# MRX80SQUARE.net
KiCad netlist of a schematic drawn in Altium Designer
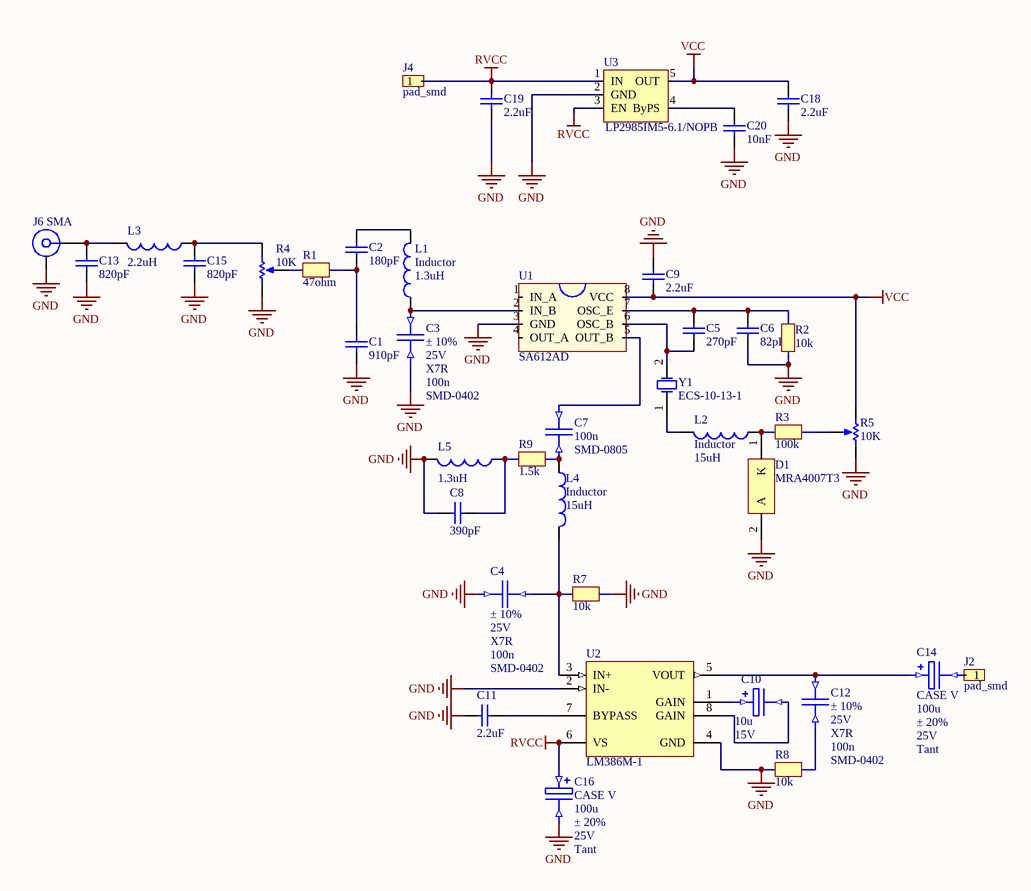
[diagram p0: MRX80SQUARE.SchDoc]

(export (version "E")
  (design (tool "Eeschema 10.0.6"))
  (components
    (comp (ref "C1")
      (value "910pF")
      (footprint "0402")
      (description "Capacitor (Semiconductor SIM Model)")
      (fields (field (name "Comment") "Cap Semi") (field (name "PUBLISHER") "Altium Limited"))
      (libsource (lib "Miscellaneous Devices") (part "Cap Semi"))
    )
    (comp (ref "C2")
      (value "180pF")
      (footprint "0402")
      (description "Capacitor (Semiconductor SIM Model)")
      (fields (field (name "Comment") "Cap Semi") (field (name "PUBLISHER") "Altium Limited"))
      (libsource (lib "Miscellaneous Devices") (part "Cap Semi"))
    )
    (comp (ref "C3")
      (value "100n")
      (footprint "CAPC1005X04N_0402")
      (description "Class 1 SMD Capacitor")
      (fields
        (field (name "MANUFACTURER") "MULTICOMP")
        (field (name "TOLERANCE") "± 10%")
        (field (name "VOLTAGE") "25V")
        (field (name "TYPE") "X7R")
        (field (name "PACKAGEREFERENCE") "SMD-0402")
        (field (name "Comment") "Capacitor")
        (field (name "PUBLISHER") "atr")
      )
      (libsource (lib "AQA_20007_4_Flange") (part "Capacitor_100n_0402_Bulk"))
    )
    (comp (ref "C4")
      (value "100n")
      (footprint "CAPC1005X04N_0402")
      (description "Class 1 SMD Capacitor")
      (fields
        (field (name "MANUFACTURER") "MULTICOMP")
        (field (name "TOLERANCE") "± 10%")
        (field (name "VOLTAGE") "25V")
        (field (name "TYPE") "X7R")
        (field (name "PACKAGEREFERENCE") "SMD-0402")
        (field (name "Comment") "Capacitor")
        (field (name "PUBLISHER") "atr")
      )
      (libsource (lib "AQA_20007_4_Flange") (part "Capacitor_100n_0402_Bulk"))
    )
    (comp (ref "C5")
      (value "270pF")
      (footprint "0402")
      (description "Capacitor (Semiconductor SIM Model)")
      (fields (field (name "Comment") "Cap Semi") (field (name "PUBLISHER") "Altium Limited"))
      (libsource (lib "Miscellaneous Devices") (part "Cap Semi"))
    )
    (comp (ref "C6")
      (value "82pF")
      (footprint "0402")
      (description "Capacitor (Semiconductor SIM Model)")
      (fields (field (name "Comment") "Cap Semi") (field (name "PUBLISHER") "Altium Limited"))
      (libsource (lib "Miscellaneous Devices") (part "Cap Semi"))
    )
    (comp (ref "C7")
      (value "100n")
      (footprint "CAPC2012X06N_0806")
      (description "Class 1 SMD Capacitor")
      (fields
        (field (name "MANUFACTURER") "Kemet")
        (field (name "TOLERANCE") "± 5%")
        (field (name "PACKAGEREFERENCE") "SMD-0805")
        (field (name "PUBLISHER") "atr")
      )
      (libsource (lib "AQA_atr_2013") (part "Capacitor_47n_0805_C0G"))
    )
    (comp (ref "C8")
      (value "390pF")
      (footprint "0402")
      (description "Capacitor (Semiconductor SIM Model)")
      (fields (field (name "Comment") "Cap Semi") (field (name "PUBLISHER") "Altium Limited"))
      (libsource (lib "Miscellaneous Devices") (part "Cap Semi"))
    )
    (comp (ref "C9")
      (value "2.2uF")
      (footprint "0402")
      (description "Capacitor (Semiconductor SIM Model)")
      (fields (field (name "Comment") "Cap Semi") (field (name "PUBLISHER") "Altium Limited"))
      (libsource (lib "Miscellaneous Devices") (part "Cap Semi"))
    )
    (comp (ref "C10")
      (value "10u")
      (footprint "CAP_CASE_B_1210_m3225")
      (description "Tant SMD Capacitor")
      (fields
        (field (name "MANUFACTURER") "AVX")
        (field (name "TOLERANCE") "± 20%")
        (field (name "VOLTAGE") "15V")
        (field (name "PUBLISHER") "atr")
      )
      (libsource (lib "AQA_atr_2013") (part "Capacitor_100u_Tant_SMD_CASE_B_m3525"))
    )
    (comp (ref "C11")
      (value "2.2uF")
      (footprint "0402")
      (description "Capacitor (Semiconductor SIM Model)")
      (fields (field (name "Comment") "Cap Semi") (field (name "PUBLISHER") "Altium Limited"))
      (libsource (lib "Miscellaneous Devices") (part "Cap Semi"))
    )
    (comp (ref "C12")
      (value "100n")
      (footprint "CAPC1005X04N_0402")
      (description "Class 1 SMD Capacitor")
      (fields
        (field (name "MANUFACTURER") "MULTICOMP")
        (field (name "TOLERANCE") "± 10%")
        (field (name "VOLTAGE") "25V")
        (field (name "TYPE") "X7R")
        (field (name "PACKAGEREFERENCE") "SMD-0402")
        (field (name "Comment") "Capacitor")
        (field (name "PUBLISHER") "atr")
      )
      (libsource (lib "AQA_20007_4_Flange") (part "Capacitor_100n_0402_Bulk"))
    )
    (comp (ref "C13")
      (value "820pF")
      (footprint "0402")
      (description "Capacitor (Semiconductor SIM Model)")
      (fields (field (name "Comment") "Cap Semi") (field (name "PUBLISHER") "Altium Limited"))
      (libsource (lib "Miscellaneous Devices") (part "Cap Semi"))
    )
    (comp (ref "C14")
      (value "100u")
      (footprint "CAP_CASE_V_2924_m7361-38")
      (description "Tant SMD Capacitor")
      (fields
        (field (name "MANUFACTURER") "AVX")
        (field (name "PACKAGEDESCRIPTION") "CASE V")
        (field (name "TOLERANCE") "± 20%")
        (field (name "VOLTAGE") "25V")
        (field (name "TYPE") "Tant")
        (field (name "Comment") "Capacitor")
        (field (name "PUBLISHER") "atr")
      )
      (libsource (lib "") (part "Capacitor_100u_Tant_SMD_CASE_V_m7361_1"))
    )
    (comp (ref "C15")
      (value "820pF")
      (footprint "0402")
      (description "Capacitor (Semiconductor SIM Model)")
      (fields (field (name "Comment") "Cap Semi") (field (name "PUBLISHER") "Altium Limited"))
      (libsource (lib "Miscellaneous Devices") (part "Cap Semi"))
    )
    (comp (ref "C16")
      (value "100u")
      (footprint "CAP_CASE_V_2924_m7361-38")
      (description "Tant SMD Capacitor")
      (fields
        (field (name "MANUFACTURER") "AVX")
        (field (name "PACKAGEDESCRIPTION") "CASE V")
        (field (name "TOLERANCE") "± 20%")
        (field (name "VOLTAGE") "25V")
        (field (name "TYPE") "Tant")
        (field (name "Comment") "Capacitor")
        (field (name "PUBLISHER") "atr")
      )
      (libsource (lib "AQA_20007_4_Flange") (part "Capacitor_100u_Tant_SMD_CASE_V_m7361"))
    )
    (comp (ref "C18")
      (value "2.2uF")
      (footprint "0402")
      (description "Capacitor (Semiconductor SIM Model)")
      (fields (field (name "Comment") "Cap Semi") (field (name "PUBLISHER") "Altium Limited"))
      (libsource (lib "Miscellaneous Devices") (part "Cap Semi"))
    )
    (comp (ref "C19")
      (value "2.2uF")
      (footprint "0402")
      (description "Capacitor (Semiconductor SIM Model)")
      (fields (field (name "Comment") "Cap Semi") (field (name "PUBLISHER") "Altium Limited"))
      (libsource (lib "Miscellaneous Devices") (part "Cap Semi"))
    )
    (comp (ref "C20")
      (value "10nF")
      (footprint "0402")
      (description "Capacitor (Semiconductor SIM Model)")
      (fields (field (name "Comment") "Cap Semi") (field (name "PUBLISHER") "Altium Limited"))
      (libsource (lib "Miscellaneous Devices") (part "Cap Semi"))
    )
    (comp (ref "D1")
      (value "MRA4007T3")
      (footprint "ONSC-SMA-2-403D-02_V")
      (description "Surface Mount Standard Recovery Power Rectifier, 2-Pin SMA, Tape and Reel")
      (fields (field (name "MANUFACTURER") "On Semiconductor"))
      (libsource (lib "ON Semi Rectifiers") (part "MRA4007T3"))
    )
    (comp (ref "J2")
      (value "pad_smd")
      (footprint "pad_smd_bodge")
      (description "1mm * 2mm smd pad")
      (libsource (lib "") (part "pad_smd_1mm*2mm_1"))
    )
    (comp (ref "J4")
      (value "pad_smd")
      (footprint "pad_smd_bodge")
      (description "1mm * 2mm smd pad")
      (libsource (lib "AQA_Ismolib") (part "pad_smd_1mm*2mm"))
    )
    (comp (ref "J6")
      (value "SMA")
      (footprint "ROS-32K145-400L5_V")
      (description "SMA Right Angle Jack, Edge Mount, Up to 18 GHz, -55 to 155 degC")
      (fields (field (name "PARTNUMBER") "32K145-400L5"))
      (libsource (lib "Rosenberger SMA") (part "32K145-400L5"))
    )
    (comp (ref "L1")
      (value "Inductor")
      (footprint "0402-A")
      (fields (field (name "ALTIUM_VALUE") "1.3uH") (field (name "PUBLISHER") "Altium Limited"))
      (libsource (lib "Miscellaneous Devices") (part "Inductor"))
    )
    (comp (ref "L2")
      (value "Inductor")
      (footprint "0402-A")
      (fields (field (name "ALTIUM_VALUE") "15uH") (field (name "PUBLISHER") "Altium Limited"))
      (libsource (lib "Miscellaneous Devices") (part "Inductor"))
    )
    (comp (ref "L3")
      (value "2.2uH")
      (footprint "0603")
      (description "Inductor")
      (fields (field (name "PUBLISHER") "Altium Limited"))
      (libsource (lib "Miscellaneous Devices") (part "Inductor"))
    )
    (comp (ref "L4")
      (value "Inductor")
      (footprint "0402-A")
      (fields (field (name "ALTIUM_VALUE") "15uH") (field (name "PUBLISHER") "Altium Limited"))
      (libsource (lib "Miscellaneous Devices") (part "Inductor"))
    )
    (comp (ref "L5")
      (value "1.3uH")
      (footprint "0402-A")
      (description "Inductor")
      (fields (field (name "PUBLISHER") "Altium Limited"))
      (libsource (lib "Miscellaneous Devices") (part "Inductor"))
    )
    (comp (ref "R1")
      (value "47ohm")
      (footprint "RESC1005X04N_0402")
      (description "Generic SMD Resistor")
      (fields
        (field (name "MANUFACTURER") "SUSUMU")
        (field (name "VOLTAGE") "75V")
        (field (name "PUBLISHER") "atr")
      )
      (libsource (lib "AQA_atr_2013") (part "Resistor_SMD_Generic"))
    )
    (comp (ref "R2")
      (value "10k")
      (footprint "RESC1005X04N_0402")
      (description "Generic SMD Resistor")
      (fields
        (field (name "MANUFACTURER") "SUSUMU")
        (field (name "VOLTAGE") "75V")
        (field (name "PUBLISHER") "atr")
      )
      (libsource (lib "") (part "Resistor_SMD_Generic_2"))
    )
    (comp (ref "R3")
      (value "100k")
      (footprint "RESC1005X04N_0402")
      (description "Generic SMD Resistor")
      (fields
        (field (name "MANUFACTURER") "SUSUMU")
        (field (name "VOLTAGE") "75V")
        (field (name "PUBLISHER") "atr")
      )
      (libsource (lib "AQA_atr_2013") (part "Resistor_SMD_Generic"))
    )
    (comp (ref "R4")
      (value "10K")
      (footprint "VR5")
      (description "Potentiometer")
      (fields (field (name "Comment") "RPot") (field (name "PUBLISHER") "Altium Limited"))
      (libsource (lib "Miscellaneous Devices") (part "RPot"))
    )
    (comp (ref "R5")
      (value "10K")
      (footprint "VR5")
      (description "Potentiometer")
      (fields (field (name "Comment") "RPot") (field (name "PUBLISHER") "Altium Limited"))
      (libsource (lib "Miscellaneous Devices") (part "RPot"))
    )
    (comp (ref "R7")
      (value "10k")
      (footprint "RESC1005X04N_0402")
      (description "Generic SMD Resistor")
      (fields
        (field (name "MANUFACTURER") "SUSUMU")
        (field (name "VOLTAGE") "75V")
        (field (name "PUBLISHER") "atr")
      )
      (libsource (lib "") (part "Resistor_SMD_Generic_1"))
    )
    (comp (ref "R8")
      (value "10k")
      (footprint "RESC1005X04N_0402")
      (description "Generic SMD Resistor")
      (fields
        (field (name "MANUFACTURER") "SUSUMU")
        (field (name "VOLTAGE") "75V")
        (field (name "PUBLISHER") "atr")
      )
      (libsource (lib "AQA_atr_2013") (part "Resistor_SMD_Generic"))
    )
    (comp (ref "R9")
      (value "1.5k")
      (footprint "RESC1608X06N_0603")
      (description "Generic SMD Resistor")
      (fields
        (field (name "MANUFACTURER") "SUSUMU")
        (field (name "VOLTAGE") "75V")
        (field (name "PUBLISHER") "atr")
      )
      (libsource (lib "AQA_atr_2013") (part "Resistor_SMD_Generic"))
    )
    (comp (ref "U1")
      (value "SA612AD")
      (footprint "SO8_SOIC8")
      (fields (field (name "SUPPLIER PART NUMBER 1") "SA612AD"))
      (libsource (lib "ftg_lib") (part "SA612AD"))
    )
    (comp (ref "U2")
      (value "LM386M-1")
      (footprint "M08A_N")
      (description "Low Voltage Audio Power Amplifier, 8-pin Narrow SOIC")
      (fields (field (name "MANUFACTURER") "National Semiconductor"))
      (libsource (lib "National Semiconductor Audio") (part "LM386M-1"))
    )
    (comp (ref "U3")
      (value "LP2985IM5-6.1/NOPB")
      (footprint "SOT23-5")
      (description "6.1V 150mA LDO")
      (fields (field (name "MANUFACTURER PART NUMBER 1") "LP2985IM5-6.1/NOPB"))
      (libsource (lib "ftg_lib") (part "LP2985IM5-6.1/NOPB"))
    )
    (comp (ref "Y1")
      (value "ECS-10-13-1")
      (footprint "HC-49U")
      (description "Crystal Oscillator")
      (fields (field (name "PUBLISHER") "Altium Limited"))
      (libsource (lib "ECS Crystal Oscillator") (part "ECS-10-13-1"))
    )
  )
  (nets
    (net (code "1") (name "GND") (class "Default")
      (node (ref "C1") (pin "1") (pinfunction "1_1") (pintype "passive"))
      (node (ref "C11") (pin "2") (pinfunction "2_2") (pintype "passive"))
      (node (ref "C13") (pin "1") (pinfunction "1_1") (pintype "passive"))
      (node (ref "C15") (pin "1") (pinfunction "1_1") (pintype "passive"))
      (node (ref "C16") (pin "2") (pinfunction "2_2") (pintype "input"))
      (node (ref "C18") (pin "1") (pinfunction "1_1") (pintype "passive"))
      (node (ref "C19") (pin "1") (pinfunction "1_1") (pintype "passive"))
      (node (ref "C20") (pin "1") (pinfunction "1_1") (pintype "passive"))
      (node (ref "C3") (pin "1") (pinfunction "1_1") (pintype "input"))
      (node (ref "C4") (pin "2") (pinfunction "2_2") (pintype "input"))
      (node (ref "C6") (pin "1") (pinfunction "1_1") (pintype "passive"))
      (node (ref "C8") (pin "2") (pinfunction "2_2") (pintype "passive"))
      (node (ref "C9") (pin "2") (pinfunction "2_2") (pintype "passive"))
      (node (ref "D1") (pin "2") (pinfunction "A_2") (pintype "passive"))
      (node (ref "J6") (pin "MP") (pinfunction "MP_MP") (pintype "passive"))
      (node (ref "L5") (pin "2") (pinfunction "2_2") (pintype "passive"))
      (node (ref "R2") (pin "1") (pinfunction "1_1") (pintype "passive"))
      (node (ref "R4") (pin "1") (pinfunction "TOP_1") (pintype "passive"))
      (node (ref "R5") (pin "2") (pinfunction "BOT_2") (pintype "passive"))
      (node (ref "R7") (pin "1") (pinfunction "1_1") (pintype "passive"))
      (node (ref "R8") (pin "1") (pinfunction "1_1") (pintype "passive"))
      (node (ref "U1") (pin "3") (pinfunction "GND_3") (pintype "passive"))
      (node (ref "U2") (pin "2") (pinfunction "IN-_2") (pintype "input"))
      (node (ref "U2") (pin "4") (pinfunction "GND_4") (pintype "power_in"))
      (node (ref "U3") (pin "2") (pinfunction "GND_2") (pintype "passive"))
    )
    (net (code "2") (name "Net-(C1-Pad2)") (class "Default")
      (node (ref "C1") (pin "2") (pinfunction "2_2") (pintype "passive"))
      (node (ref "C2") (pin "1") (pinfunction "1_1") (pintype "passive"))
      (node (ref "R1") (pin "2") (pinfunction "2_2") (pintype "passive"))
    )
    (net (code "3") (name "Net-(C2-Pad2)") (class "Default")
      (node (ref "C2") (pin "2") (pinfunction "2_2") (pintype "passive"))
      (node (ref "L1") (pin "2") (pinfunction "2_2") (pintype "passive"))
    )
    (net (code "4") (name "Net-(C7-Pad1)") (class "Default")
      (node (ref "C7") (pin "1") (pinfunction "1_1") (pintype "input"))
      (node (ref "L4") (pin "1") (pinfunction "1_1") (pintype "passive"))
      (node (ref "R9") (pin "2") (pinfunction "2_2") (pintype "passive"))
    )
    (net (code "5") (name "Net-(C8-Pad1)") (class "Default")
      (node (ref "C8") (pin "1") (pinfunction "1_1") (pintype "passive"))
      (node (ref "L5") (pin "1") (pinfunction "1_1") (pintype "passive"))
      (node (ref "R9") (pin "1") (pinfunction "1_1") (pintype "passive"))
    )
    (net (code "6") (name "Net-(C10-Pad1)") (class "Default")
      (node (ref "C10") (pin "1") (pinfunction "1_1") (pintype "input"))
      (node (ref "U2") (pin "1") (pinfunction "GAIN_1") (pintype "passive"))
    )
    (net (code "7") (name "Net-(C10-Pad2)") (class "Default")
      (node (ref "C10") (pin "2") (pinfunction "2_2") (pintype "input"))
      (node (ref "U2") (pin "8") (pinfunction "GAIN_8") (pintype "passive"))
    )
    (net (code "8") (name "Net-(C12-Pad1)") (class "Default")
      (node (ref "C12") (pin "1") (pinfunction "1_1") (pintype "input"))
      (node (ref "R8") (pin "2") (pinfunction "2_2") (pintype "passive"))
    )
    (net (code "9") (name "Net-(C13-Pad2)") (class "Default")
      (node (ref "C13") (pin "2") (pinfunction "2_2") (pintype "passive"))
      (node (ref "J6") (pin "1") (pinfunction "1_1") (pintype "passive"))
      (node (ref "L3") (pin "2") (pinfunction "2_2") (pintype "passive"))
    )
    (net (code "10") (name "Net-(C14-Pad2)") (class "Default")
      (node (ref "C14") (pin "2") (pinfunction "2_2") (pintype "input"))
      (node (ref "J2") (pin "1") (pinfunction "1_1") (pintype "passive"))
    )
    (net (code "11") (name "Net-(D1-K)") (class "Default")
      (node (ref "D1") (pin "1") (pinfunction "K_1") (pintype "passive"))
      (node (ref "L2") (pin "1") (pinfunction "1_1") (pintype "passive"))
      (node (ref "R3") (pin "1") (pinfunction "1_1") (pintype "passive"))
    )
    (net (code "12") (name "Net-(R4-BOT)") (class "Default")
      (node (ref "C15") (pin "2") (pinfunction "2_2") (pintype "passive"))
      (node (ref "L3") (pin "1") (pinfunction "1_1") (pintype "passive"))
      (node (ref "R4") (pin "2") (pinfunction "BOT_2") (pintype "passive"))
    )
    (net (code "13") (name "Net-(R4-TAP)") (class "Default")
      (node (ref "R1") (pin "1") (pinfunction "1_1") (pintype "passive"))
      (node (ref "R4") (pin "3") (pinfunction "TAP_3") (pintype "passive"))
    )
    (net (code "14") (name "Net-(R5-TAP)") (class "Default")
      (node (ref "R3") (pin "2") (pinfunction "2_2") (pintype "passive"))
      (node (ref "R5") (pin "3") (pinfunction "TAP_3") (pintype "passive"))
    )
    (net (code "15") (name "Net-(U1-IN_B)") (class "Default")
      (node (ref "C3") (pin "2") (pinfunction "2_2") (pintype "input"))
      (node (ref "L1") (pin "1") (pinfunction "1_1") (pintype "passive"))
      (node (ref "U1") (pin "2") (pinfunction "IN_B_2") (pintype "passive"))
    )
    (net (code "16") (name "Net-(U1-OSC_B)") (class "Default")
      (node (ref "C5") (pin "1") (pinfunction "1_1") (pintype "passive"))
      (node (ref "U1") (pin "6") (pinfunction "OSC_B_6") (pintype "passive"))
      (node (ref "Y1") (pin "2") (pinfunction "OSC2_2") (pintype "passive"))
    )
    (net (code "17") (name "Net-(U1-OSC_E)") (class "Default")
      (node (ref "C5") (pin "2") (pinfunction "2_2") (pintype "passive"))
      (node (ref "C6") (pin "2") (pinfunction "2_2") (pintype "passive"))
      (node (ref "R2") (pin "2") (pinfunction "2_2") (pintype "passive"))
      (node (ref "U1") (pin "7") (pinfunction "OSC_E_7") (pintype "passive"))
    )
    (net (code "18") (name "Net-(U1-OUT_B)") (class "Default")
      (node (ref "C7") (pin "2") (pinfunction "2_2") (pintype "input"))
      (node (ref "U1") (pin "5") (pinfunction "OUT_B_5") (pintype "passive"))
    )
    (net (code "19") (name "Net-(U2-BYPASS)") (class "Default")
      (node (ref "C11") (pin "1") (pinfunction "1_1") (pintype "passive"))
      (node (ref "U2") (pin "7") (pinfunction "BYPASS_7") (pintype "passive"))
    )
    (net (code "20") (name "Net-(U2-IN+)") (class "Default")
      (node (ref "C4") (pin "1") (pinfunction "1_1") (pintype "input"))
      (node (ref "L4") (pin "2") (pinfunction "2_2") (pintype "passive"))
      (node (ref "R7") (pin "2") (pinfunction "2_2") (pintype "passive"))
      (node (ref "U2") (pin "3") (pinfunction "IN+_3") (pintype "input"))
    )
    (net (code "21") (name "Net-(U2-VOUT)") (class "Default")
      (node (ref "C12") (pin "2") (pinfunction "2_2") (pintype "input"))
      (node (ref "C14") (pin "1") (pinfunction "1_1") (pintype "input"))
      (node (ref "U2") (pin "5") (pinfunction "VOUT_5") (pintype "output"))
    )
    (net (code "22") (name "Net-(U3-ByPS)") (class "Default")
      (node (ref "C20") (pin "2") (pinfunction "2_2") (pintype "passive"))
      (node (ref "U3") (pin "4") (pinfunction "ByPS_4") (pintype "passive"))
    )
    (net (code "23") (name "Net-(Y1-OSC1)") (class "Default")
      (node (ref "L2") (pin "2") (pinfunction "2_2") (pintype "passive"))
      (node (ref "Y1") (pin "1") (pinfunction "OSC1_1") (pintype "passive"))
    )
    (net (code "24") (name "RVCC") (class "Default")
      (node (ref "C16") (pin "1") (pinfunction "1_1") (pintype "input"))
      (node (ref "C19") (pin "2") (pinfunction "2_2") (pintype "passive"))
      (node (ref "J4") (pin "1") (pinfunction "1_1") (pintype "passive"))
      (node (ref "U2") (pin "6") (pinfunction "VS_6") (pintype "power_in"))
      (node (ref "U3") (pin "1") (pinfunction "IN_1") (pintype "passive"))
      (node (ref "U3") (pin "3") (pinfunction "EN_3") (pintype "passive"))
    )
    (net (code "25") (name "VCC") (class "Default")
      (node (ref "C18") (pin "2") (pinfunction "2_2") (pintype "passive"))
      (node (ref "C9") (pin "1") (pinfunction "1_1") (pintype "passive"))
      (node (ref "R5") (pin "1") (pinfunction "TOP_1") (pintype "passive"))
      (node (ref "U1") (pin "8") (pinfunction "VCC_8") (pintype "passive"))
      (node (ref "U3") (pin "5") (pinfunction "OUT_5") (pintype "passive"))
    )
    (net (code "26") (name "unconnected-(U1-IN_A-Pad1)") (class "Default")
      (node (ref "U1") (pin "1") (pinfunction "IN_A_1") (pintype "passive"))
    )
    (net (code "27") (name "unconnected-(U1-OUT_A-Pad4)") (class "Default")
      (node (ref "U1") (pin "4") (pinfunction "OUT_A_4") (pintype "passive"))
    )
  )
)
